# Input_Buffer.net
KiCad netlist of a schematic drawn in Altium Designer
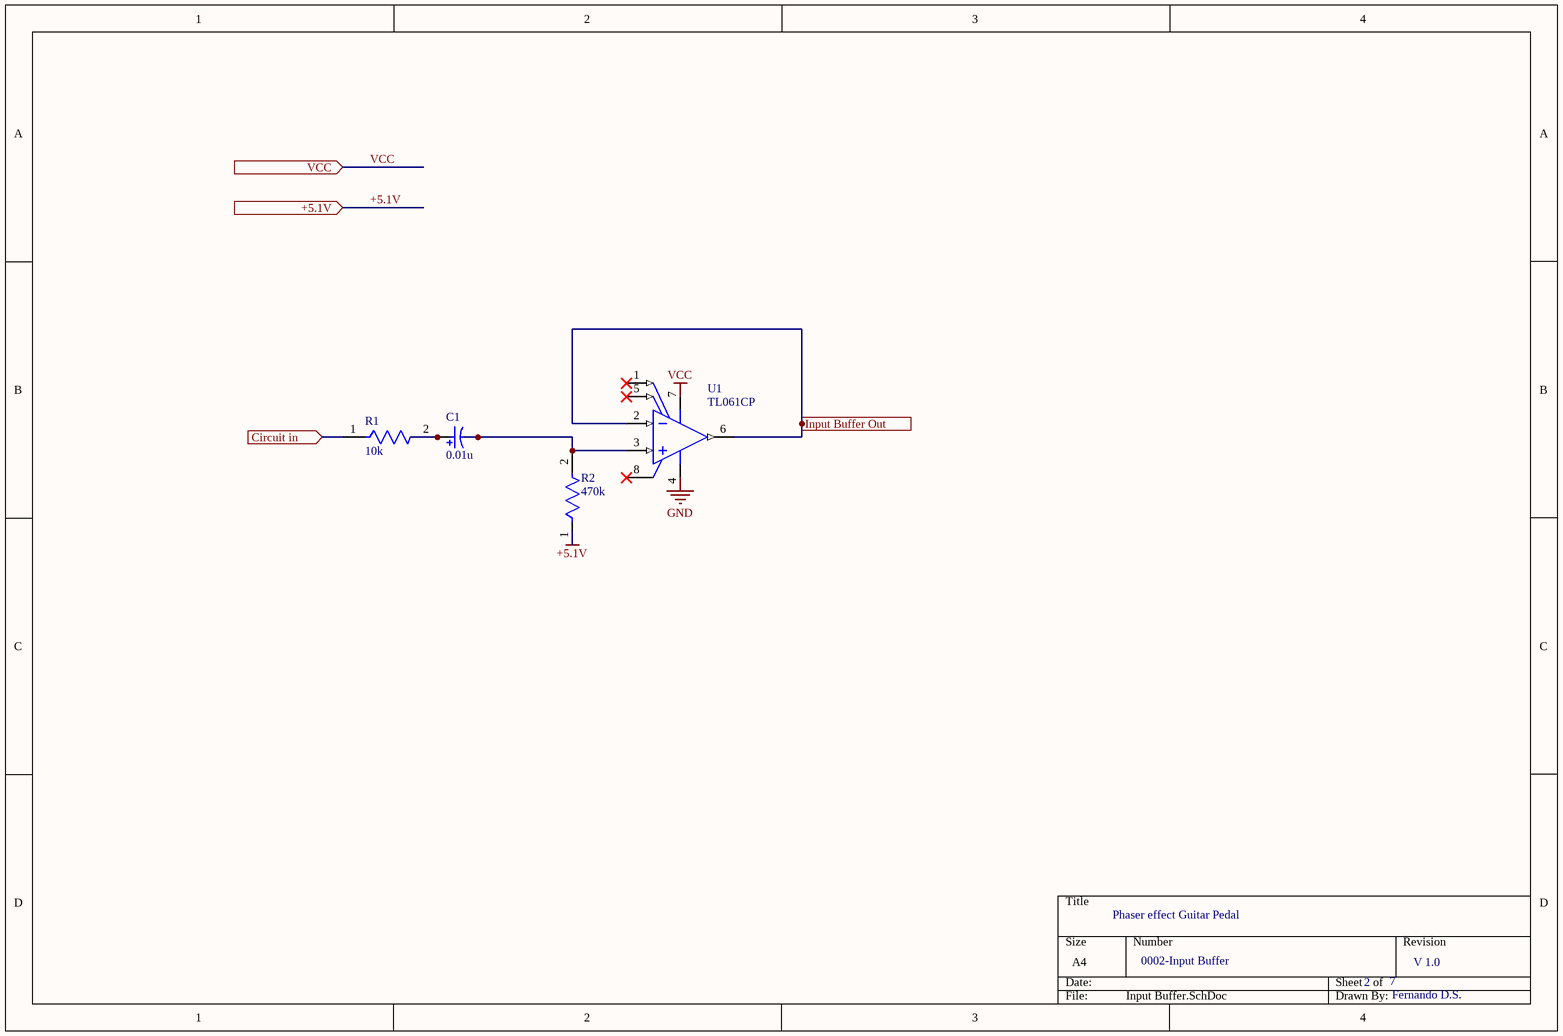
[diagram p0: Input Buffer.SchDoc]

(export (version "E")
  (design (tool "Eeschema 10.0.6"))
  (components
    (comp (ref "C1")
      (value "0.01u")
      (footprint "NIC-PLF-10x13-2_V")
      (description "Aluminum Electrolytic Capacitor, 470 uF +/-20%, 10 V, -55 to 105 degC, 2-Pin THD, RoHS")
      (fields (field (name "MANUFACTURER") "Nichicon") (field (name "PARTNUMBER") "PLF1A471MDO1"))
      (libsource (lib "Altium Content Vault") (part "NIC-CAP-P-2"))
    )
    (comp (ref "R1")
      (value "10k")
      (footprint "FP-MRS25-MFG")
      (fields (field (name "TOLERANCE") "1%"))
      (libsource (lib "Altium Content Vault") (part "1029c3af85768c4190bb7ad29bc67b5"))
    )
    (comp (ref "R2")
      (value "470k")
      (footprint "FP-MRS25-MFG")
      (fields (field (name "TOLERANCE") "1%"))
      (libsource (lib "Altium Content Vault") (part "1029c3af85768c4190bb7ad29bc67b5"))
    )
    (comp (ref "U1")
      (value "TL061CP")
      (footprint "P0008A")
      (fields (field (name "MANUFACTURER") "Texas Instruments"))
      (libsource (lib "Altium Content Vault") (part "TI-AMP-S5-2-8"))
    )
  )
  (nets
    (net (code "1") (name "+5.1V") (class "Default")
      (node (ref "R2") (pin "1") (pinfunction "1_1") (pintype "passive"))
    )
    (net (code "2") (name "/Circuit in") (class "Default")
      (node (ref "R1") (pin "1") (pinfunction "1_1") (pintype "passive"))
    )
    (net (code "3") (name "/Input Buffer Out") (class "Default")
      (node (ref "U1") (pin "2") (pinfunction "IN-_2") (pintype "input"))
      (node (ref "U1") (pin "6") (pinfunction "OUT_6") (pintype "output"))
    )
    (net (code "5") (name "Net-(C1-Pad1)") (class "Default")
      (node (ref "C1") (pin "1") (pinfunction "1_1") (pintype "passive"))
      (node (ref "R1") (pin "2") (pinfunction "2_2") (pintype "passive"))
    )
    (net (code "6") (name "Net-(U1-IN+)") (class "Default")
      (node (ref "C1") (pin "2") (pinfunction "2_2") (pintype "passive"))
      (node (ref "R2") (pin "2") (pinfunction "2_2") (pintype "passive"))
      (node (ref "U1") (pin "3") (pinfunction "IN+_3") (pintype "input"))
    )
    (net (code "8") (name "unconnected-(U1-NC-Pad8)") (class "Default")
      (node (ref "U1") (pin "8") (pinfunction "NC_8") (pintype "passive+no_connect"))
    )
    (net (code "9") (name "unconnected-(U1-OFFSET_N1-Pad1)") (class "Default")
      (node (ref "U1") (pin "1") (pinfunction "OFFSET_N1_1") (pintype "input+no_connect"))
    )
    (net (code "10") (name "unconnected-(U1-OFFSET_N2-Pad5)") (class "Default")
      (node (ref "U1") (pin "5") (pinfunction "OFFSET_N2_5") (pintype "input+no_connect"))
    )
    (net (code "11") (name "unconnected-(U1-VCC+-Pad7)") (class "Default")
      (node (ref "U1") (pin "7") (pinfunction "VCC+_7") (pintype "power_in"))
    )
    (net (code "12") (name "unconnected-(U1-VCC--Pad4)") (class "Default")
      (node (ref "U1") (pin "4") (pinfunction "VCC-_4") (pintype "power_in"))
    )
  )
)
